# design.net
KiCad netlist of a schematic drawn in Altium Designer
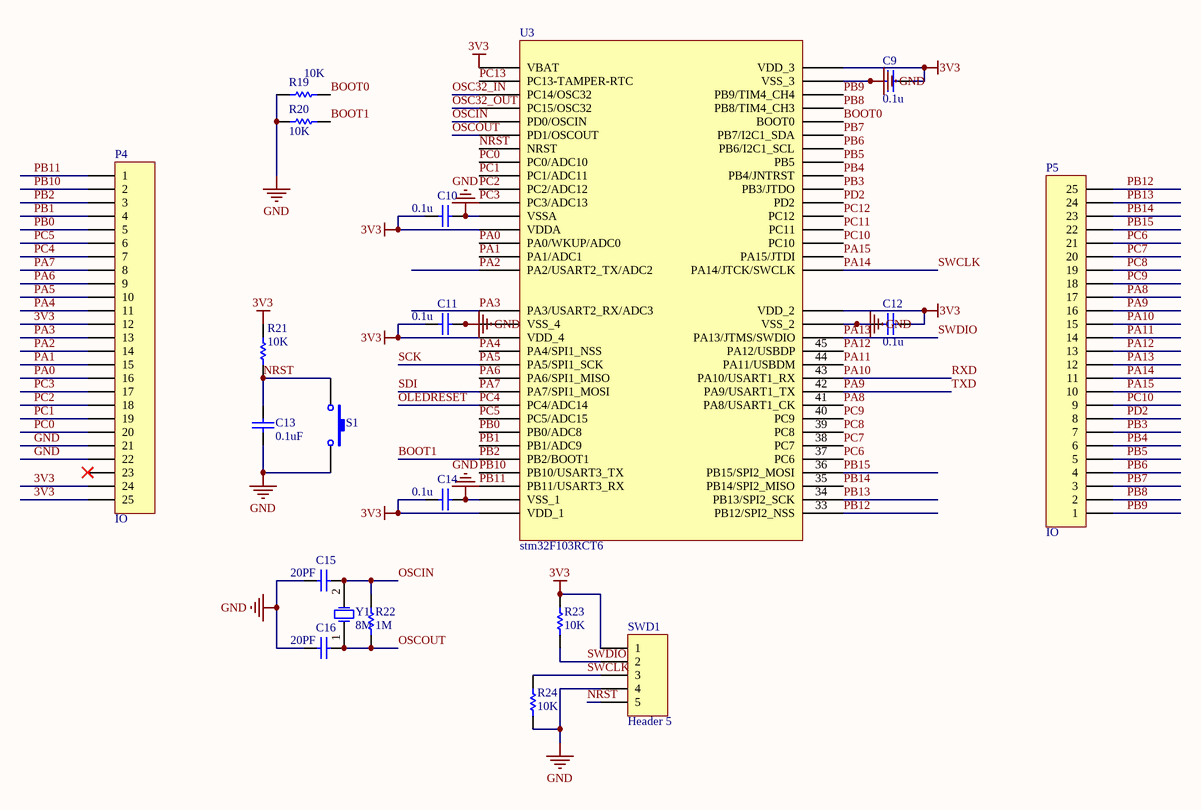
[diagram p0: 最小系统.SchDoc]

(export (version "E")
  (design (tool "Eeschema 10.0.6"))
  (components
    (comp (ref "C9")
      (value "0.1u")
      (footprint "CAP-MLCC-0603")
      (description "Capacitor")
      (fields (field (name "Comment") "Cap") (field (name "PUBLISHER") "Altium Limited"))
      (libsource (lib "K60-mainboard-v3.1") (part "Cap_1"))
    )
    (comp (ref "C10")
      (value "0.1u")
      (footprint "CAP-MLCC-0603")
      (description "Capacitor")
      (fields (field (name "Comment") "Cap") (field (name "PUBLISHER") "Altium Limited"))
      (libsource (lib "K60-mainboard-v3.1") (part "Cap_1"))
    )
    (comp (ref "C11")
      (value "0.1u")
      (footprint "CAP-MLCC-0603")
      (description "Capacitor")
      (fields (field (name "Comment") "Cap") (field (name "PUBLISHER") "Altium Limited"))
      (libsource (lib "K60-mainboard-v3.1") (part "Cap_1"))
    )
    (comp (ref "C12")
      (value "0.1u")
      (footprint "CAP-MLCC-0603")
      (description "Capacitor")
      (fields (field (name "Comment") "Cap") (field (name "PUBLISHER") "Altium Limited"))
      (libsource (lib "K60-mainboard-v3.1") (part "Cap_1"))
    )
    (comp (ref "C13")
      (value "0.1uF")
      (footprint "CAP-MLCC-0603")
      (description "Capacitor")
      (fields (field (name "Comment") "Cap") (field (name "PUBLISHER") "Altium Limited"))
      (libsource (lib "K60-mainboard-v3.1") (part "Cap"))
    )
    (comp (ref "C14")
      (value "0.1u")
      (footprint "CAP-MLCC-0603")
      (description "Capacitor")
      (fields (field (name "Comment") "Cap") (field (name "PUBLISHER") "Altium Limited"))
      (libsource (lib "K60-mainboard-v3.1") (part "Cap_1"))
    )
    (comp (ref "C15")
      (value "20PF")
      (footprint "CAP-MLCC-0603")
      (description "Capacitor")
      (fields (field (name "Comment") "Cap") (field (name "PUBLISHER") "Altium Limited"))
      (libsource (lib "K60-mainboard-v3.1") (part "Cap_1"))
    )
    (comp (ref "C16")
      (value "20PF")
      (footprint "CAP-MLCC-0603")
      (description "Capacitor")
      (fields (field (name "Comment") "Cap") (field (name "PUBLISHER") "Altium Limited"))
      (libsource (lib "K60-mainboard-v3.1") (part "Cap_1"))
    )
    (comp (ref "P4")
      (value "IO")
      (footprint "Header 25")
      (description "Header, 25-Pin")
      (fields (field (name "PUBLISHER") "Altium Limited"))
      (libsource (lib "") (part "Header 25_1"))
    )
    (comp (ref "P5")
      (value "IO")
      (footprint "Header 25")
      (description "Header, 25-Pin")
      (fields (field (name "PUBLISHER") "Altium Limited"))
      (libsource (lib "Libraries_2014_0618") (part "Header 25"))
    )
    (comp (ref "R19")
      (value "10K")
      (footprint "RES-0603")
      (description "Resistor")
      (fields (field (name "Comment") "Res1") (field (name "PUBLISHER") "Altium Limited"))
      (libsource (lib "K60-mainboard-v3.1") (part "Res1_1"))
    )
    (comp (ref "R20")
      (value "10K")
      (footprint "RES-0603")
      (description "Resistor")
      (fields (field (name "Comment") "Res1") (field (name "PUBLISHER") "Altium Limited"))
      (libsource (lib "K60-mainboard-v3.1") (part "Res1_1"))
    )
    (comp (ref "R21")
      (value "10K")
      (footprint "RES-0603")
      (description "Resistor")
      (fields (field (name "Comment") "Res1") (field (name "PUBLISHER") "Altium Limited"))
      (libsource (lib "K60-mainboard-v3.1") (part "Res1_1"))
    )
    (comp (ref "R22")
      (value "1M")
      (footprint "RES-0603")
      (description "Resistor")
      (fields (field (name "Comment") "Res1") (field (name "PUBLISHER") "Altium Limited"))
      (libsource (lib "K60-mainboard-v3.1") (part "Res1_1"))
    )
    (comp (ref "R23")
      (value "10K")
      (footprint "RES-0603")
      (description "Resistor")
      (fields (field (name "Comment") "Res1") (field (name "PUBLISHER") "Altium Limited"))
      (libsource (lib "K60-mainboard-v3.1") (part "Res1_1"))
    )
    (comp (ref "R24")
      (value "10K")
      (footprint "RES-0603")
      (description "Resistor")
      (fields (field (name "Comment") "Res1") (field (name "PUBLISHER") "Altium Limited"))
      (libsource (lib "K60-mainboard-v3.1") (part "Res1_1"))
    )
    (comp (ref "S1")
      (value "SW-PB")
      (footprint "key - duplicate")
      (description "Switch")
      (fields (field (name "PUBLISHER") "Altium Limited"))
      (libsource (lib "附加元件") (part "SW-PB"))
    )
    (comp (ref "SWD1")
      (value "Header 5")
      (footprint "HDR1X5")
      (description "Header, 5-Pin")
      (fields (field (name "PUBLISHER") "Altium Limited"))
      (libsource (lib "K60-mainboard-v3.1") (part "Header 5"))
    )
    (comp (ref "U3")
      (value "stm32F103RCT6")
      (footprint "STM32F103RCT6")
      (libsource (lib "K60-mainboard-v3.1") (part "stm32F103RCT6"))
    )
    (comp (ref "Y1")
      (value "8M")
      (footprint "Libraries_2014_0618:Osc-6032")
      (description "Crystal Oscillator")
      (fields (field (name "PUBLISHER") "Altium Limited"))
      (libsource (lib "Libraries_2014_0618") (part "C-Osc"))
    )
  )
  (nets
    (net (code "1") (name "/BOOT0") (class "Default")
      (node (ref "R19") (pin "1") (pinfunction "1_1") (pintype "passive"))
      (node (ref "U3") (pin "60") (pinfunction "BOOT0_60") (pintype "passive"))
    )
    (net (code "2") (name "/BOOT1") (class "Default")
      (node (ref "P4") (pin "3") (pinfunction "3_3") (pintype "passive"))
      (node (ref "R20") (pin "1") (pinfunction "1_1") (pintype "passive"))
      (node (ref "U3") (pin "28") (pinfunction "PB2/BOOT1_28") (pintype "passive"))
    )
    (net (code "3") (name "/NRST") (class "Default")
      (node (ref "C13") (pin "1") (pinfunction "1_1") (pintype "passive"))
      (node (ref "R21") (pin "1") (pinfunction "1_1") (pintype "passive"))
      (node (ref "S1") (pin "1") (pinfunction "1_1") (pintype "passive"))
      (node (ref "SWD1") (pin "5") (pinfunction "5_5") (pintype "passive"))
      (node (ref "U3") (pin "7") (pinfunction "NRST_7") (pintype "passive"))
    )
    (net (code "4") (name "/OLEDRESET") (class "Default")
      (node (ref "P4") (pin "7") (pinfunction "7_7") (pintype "passive"))
      (node (ref "U3") (pin "24") (pinfunction "PC4/ADC14_24") (pintype "passive"))
    )
    (net (code "5") (name "/OSC32_IN") (class "Default")
      (node (ref "U3") (pin "3") (pinfunction "PC14/OSC32_3") (pintype "passive"))
    )
    (net (code "6") (name "/OSC32_OUT") (class "Default")
      (node (ref "U3") (pin "4") (pinfunction "PC15/OSC32_4") (pintype "passive"))
    )
    (net (code "7") (name "/OSCIN") (class "Default")
      (node (ref "C15") (pin "2") (pinfunction "2_2") (pintype "passive"))
      (node (ref "R22") (pin "2") (pinfunction "2_2") (pintype "passive"))
      (node (ref "U3") (pin "5") (pinfunction "PD0/OSCIN_5") (pintype "passive"))
      (node (ref "Y1") (pin "2") (pinfunction "OSC2_2") (pintype "passive"))
    )
    (net (code "8") (name "/OSCOUT") (class "Default")
      (node (ref "C16") (pin "2") (pinfunction "2_2") (pintype "passive"))
      (node (ref "R22") (pin "1") (pinfunction "1_1") (pintype "passive"))
      (node (ref "U3") (pin "6") (pinfunction "PD1/OSCOUT_6") (pintype "passive"))
      (node (ref "Y1") (pin "1") (pinfunction "OSC1_1") (pintype "passive"))
    )
    (net (code "9") (name "/PA0") (class "Default")
      (node (ref "P4") (pin "16") (pinfunction "16_16") (pintype "passive"))
      (node (ref "U3") (pin "14") (pinfunction "PA0/WKUP/ADC0_14") (pintype "passive"))
    )
    (net (code "10") (name "/PA1") (class "Default")
      (node (ref "P4") (pin "15") (pinfunction "15_15") (pintype "passive"))
      (node (ref "U3") (pin "15") (pinfunction "PA1/ADC1_15") (pintype "passive"))
    )
    (net (code "11") (name "/PA2") (class "Default")
      (node (ref "P4") (pin "14") (pinfunction "14_14") (pintype "passive"))
      (node (ref "U3") (pin "16") (pinfunction "PA2/USART2_TX/ADC2_16") (pintype "passive"))
    )
    (net (code "12") (name "/PA3") (class "Default")
      (node (ref "P4") (pin "13") (pinfunction "13_13") (pintype "passive"))
      (node (ref "U3") (pin "17") (pinfunction "PA3/USART2_RX/ADC3_17") (pintype "passive"))
    )
    (net (code "13") (name "/PA4") (class "Default")
      (node (ref "P4") (pin "11") (pinfunction "11_11") (pintype "passive"))
      (node (ref "U3") (pin "20") (pinfunction "PA4/SPI1_NSS_20") (pintype "passive"))
    )
    (net (code "14") (name "/PA5") (class "Default")
      (node (ref "P4") (pin "10") (pinfunction "10_10") (pintype "passive"))
      (node (ref "U3") (pin "21") (pinfunction "PA5/SPI1_SCK_21") (pintype "passive"))
    )
    (net (code "15") (name "/PA6") (class "Default")
      (node (ref "P4") (pin "9") (pinfunction "9_9") (pintype "passive"))
      (node (ref "U3") (pin "22") (pinfunction "PA6/SPI1_MISO_22") (pintype "passive"))
    )
    (net (code "16") (name "/PA7") (class "Default")
      (node (ref "P4") (pin "8") (pinfunction "8_8") (pintype "passive"))
      (node (ref "U3") (pin "23") (pinfunction "PA7/SPI1_MOSI_23") (pintype "passive"))
    )
    (net (code "17") (name "/PA8") (class "Default")
      (node (ref "P5") (pin "17") (pinfunction "17_17") (pintype "passive"))
      (node (ref "U3") (pin "41") (pinfunction "PA8/USART1_CK_41") (pintype "passive"))
    )
    (net (code "18") (name "/PA9") (class "Default")
      (node (ref "P5") (pin "16") (pinfunction "16_16") (pintype "passive"))
      (node (ref "U3") (pin "42") (pinfunction "PA9/USART1_TX_42") (pintype "passive"))
    )
    (net (code "19") (name "/PA10") (class "Default")
      (node (ref "P5") (pin "15") (pinfunction "15_15") (pintype "passive"))
      (node (ref "U3") (pin "43") (pinfunction "PA10/USART1_RX_43") (pintype "passive"))
    )
    (net (code "20") (name "/PA11") (class "Default")
      (node (ref "P5") (pin "14") (pinfunction "14_14") (pintype "passive"))
      (node (ref "U3") (pin "44") (pinfunction "PA11/USBDM_44") (pintype "passive"))
    )
    (net (code "21") (name "/PA12") (class "Default")
      (node (ref "P5") (pin "13") (pinfunction "13_13") (pintype "passive"))
      (node (ref "U3") (pin "45") (pinfunction "PA12/USBDP_45") (pintype "passive"))
    )
    (net (code "22") (name "/PA13") (class "Default")
      (node (ref "P5") (pin "12") (pinfunction "12_12") (pintype "passive"))
      (node (ref "R23") (pin "1") (pinfunction "1_1") (pintype "passive"))
      (node (ref "SWD1") (pin "2") (pinfunction "2_2") (pintype "passive"))
      (node (ref "U3") (pin "46") (pinfunction "PA13/JTMS/SWDIO_46") (pintype "passive"))
    )
    (net (code "23") (name "/PA14") (class "Default")
      (node (ref "P5") (pin "11") (pinfunction "11_11") (pintype "passive"))
      (node (ref "R24") (pin "1") (pinfunction "1_1") (pintype "passive"))
      (node (ref "SWD1") (pin "3") (pinfunction "3_3") (pintype "passive"))
      (node (ref "U3") (pin "49") (pinfunction "PA14/JTCK/SWCLK_49") (pintype "passive"))
    )
    (net (code "24") (name "/PA15") (class "Default")
      (node (ref "P5") (pin "10") (pinfunction "10_10") (pintype "passive"))
      (node (ref "U3") (pin "50") (pinfunction "PA15/JTDI_50") (pintype "passive"))
    )
    (net (code "25") (name "/PB0") (class "Default")
      (node (ref "P4") (pin "5") (pinfunction "5_5") (pintype "passive"))
      (node (ref "U3") (pin "26") (pinfunction "PB0/ADC8_26") (pintype "passive"))
    )
    (net (code "26") (name "/PB1") (class "Default")
      (node (ref "P4") (pin "4") (pinfunction "4_4") (pintype "passive"))
      (node (ref "U3") (pin "27") (pinfunction "PB1/ADC9_27") (pintype "passive"))
    )
    (net (code "27") (name "/PB3") (class "Default")
      (node (ref "P5") (pin "7") (pinfunction "7_7") (pintype "passive"))
      (node (ref "U3") (pin "55") (pinfunction "PB3/JTDO_55") (pintype "passive"))
    )
    (net (code "28") (name "/PB4") (class "Default")
      (node (ref "P5") (pin "6") (pinfunction "6_6") (pintype "passive"))
      (node (ref "U3") (pin "56") (pinfunction "PB4/JNTRST_56") (pintype "passive"))
    )
    (net (code "29") (name "/PB5") (class "Default")
      (node (ref "P5") (pin "5") (pinfunction "5_5") (pintype "passive"))
      (node (ref "U3") (pin "57") (pinfunction "PB5_57") (pintype "passive"))
    )
    (net (code "30") (name "/PB6") (class "Default")
      (node (ref "P5") (pin "4") (pinfunction "4_4") (pintype "passive"))
      (node (ref "U3") (pin "58") (pinfunction "PB6/I2C1_SCL_58") (pintype "passive"))
    )
    (net (code "31") (name "/PB7") (class "Default")
      (node (ref "P5") (pin "3") (pinfunction "3_3") (pintype "passive"))
      (node (ref "U3") (pin "59") (pinfunction "PB7/I2C1_SDA_59") (pintype "passive"))
    )
    (net (code "32") (name "/PB8") (class "Default")
      (node (ref "P5") (pin "2") (pinfunction "2_2") (pintype "passive"))
      (node (ref "U3") (pin "61") (pinfunction "PB8/TIM4_CH3_61") (pintype "passive"))
    )
    (net (code "33") (name "/PB9") (class "Default")
      (node (ref "P5") (pin "1") (pinfunction "1_1") (pintype "passive"))
      (node (ref "U3") (pin "62") (pinfunction "PB9/TIM4_CH4_62") (pintype "passive"))
    )
    (net (code "34") (name "/PB10") (class "Default")
      (node (ref "P4") (pin "2") (pinfunction "2_2") (pintype "passive"))
      (node (ref "U3") (pin "29") (pinfunction "PB10/USART3_TX_29") (pintype "passive"))
    )
    (net (code "35") (name "/PB11") (class "Default")
      (node (ref "P4") (pin "1") (pinfunction "1_1") (pintype "passive"))
      (node (ref "U3") (pin "30") (pinfunction "PB11/USART3_RX_30") (pintype "passive"))
    )
    (net (code "36") (name "/PB12") (class "Default")
      (node (ref "P5") (pin "25") (pinfunction "25_25") (pintype "passive"))
      (node (ref "U3") (pin "33") (pinfunction "PB12/SPI2_NSS_33") (pintype "passive"))
    )
    (net (code "37") (name "/PB13") (class "Default")
      (node (ref "P5") (pin "24") (pinfunction "24_24") (pintype "passive"))
      (node (ref "U3") (pin "34") (pinfunction "PB13/SPI2_SCK_34") (pintype "passive"))
    )
    (net (code "38") (name "/PB14") (class "Default")
      (node (ref "P5") (pin "23") (pinfunction "23_23") (pintype "passive"))
      (node (ref "U3") (pin "35") (pinfunction "PB14/SPI2_MISO_35") (pintype "passive"))
    )
    (net (code "39") (name "/PB15") (class "Default")
      (node (ref "P5") (pin "22") (pinfunction "22_22") (pintype "passive"))
      (node (ref "U3") (pin "36") (pinfunction "PB15/SPI2_MOSI_36") (pintype "passive"))
    )
    (net (code "40") (name "/PC0") (class "Default")
      (node (ref "P4") (pin "20") (pinfunction "20_20") (pintype "passive"))
      (node (ref "U3") (pin "8") (pinfunction "PC0/ADC10_8") (pintype "passive"))
    )
    (net (code "41") (name "/PC1") (class "Default")
      (node (ref "P4") (pin "19") (pinfunction "19_19") (pintype "passive"))
      (node (ref "U3") (pin "9") (pinfunction "PC1/ADC11_9") (pintype "passive"))
    )
    (net (code "42") (name "/PC2") (class "Default")
      (node (ref "P4") (pin "18") (pinfunction "18_18") (pintype "passive"))
      (node (ref "U3") (pin "10") (pinfunction "PC2/ADC12_10") (pintype "passive"))
    )
    (net (code "43") (name "/PC3") (class "Default")
      (node (ref "P4") (pin "17") (pinfunction "17_17") (pintype "passive"))
      (node (ref "U3") (pin "11") (pinfunction "PC3/ADC13_11") (pintype "passive"))
    )
    (net (code "44") (name "/PC5") (class "Default")
      (node (ref "P4") (pin "6") (pinfunction "6_6") (pintype "passive"))
      (node (ref "U3") (pin "25") (pinfunction "PC5/ADC15_25") (pintype "passive"))
    )
    (net (code "45") (name "/PC6") (class "Default")
      (node (ref "P5") (pin "21") (pinfunction "21_21") (pintype "passive"))
      (node (ref "U3") (pin "37") (pinfunction "PC6_37") (pintype "passive"))
    )
    (net (code "46") (name "/PC7") (class "Default")
      (node (ref "P5") (pin "20") (pinfunction "20_20") (pintype "passive"))
      (node (ref "U3") (pin "38") (pinfunction "PC7_38") (pintype "passive"))
    )
    (net (code "47") (name "/PC8") (class "Default")
      (node (ref "P5") (pin "19") (pinfunction "19_19") (pintype "passive"))
      (node (ref "U3") (pin "39") (pinfunction "PC8_39") (pintype "passive"))
    )
    (net (code "48") (name "/PC9") (class "Default")
      (node (ref "P5") (pin "18") (pinfunction "18_18") (pintype "passive"))
      (node (ref "U3") (pin "40") (pinfunction "PC9_40") (pintype "passive"))
    )
    (net (code "49") (name "/PC10") (class "Default")
      (node (ref "P5") (pin "9") (pinfunction "9_9") (pintype "passive"))
      (node (ref "U3") (pin "51") (pinfunction "PC10_51") (pintype "passive"))
    )
    (net (code "50") (name "/PC11") (class "Default")
      (node (ref "U3") (pin "52") (pinfunction "PC11_52") (pintype "passive"))
    )
    (net (code "51") (name "/PC12") (class "Default")
      (node (ref "U3") (pin "53") (pinfunction "PC12_53") (pintype "passive"))
    )
    (net (code "52") (name "/PC13") (class "Default")
      (node (ref "U3") (pin "2") (pinfunction "PC13-TAMPER-RTC_2") (pintype "passive"))
    )
    (net (code "53") (name "/PD2") (class "Default")
      (node (ref "P5") (pin "8") (pinfunction "8_8") (pintype "passive"))
      (node (ref "U3") (pin "54") (pinfunction "PD2_54") (pintype "passive"))
    )
    (net (code "54") (name "3V3") (class "Default")
      (node (ref "C10") (pin "1") (pinfunction "1_1") (pintype "passive"))
      (node (ref "C11") (pin "1") (pinfunction "1_1") (pintype "passive"))
      (node (ref "C12") (pin "1") (pinfunction "1_1") (pintype "passive"))
      (node (ref "C14") (pin "1") (pinfunction "1_1") (pintype "passive"))
      (node (ref "C9") (pin "1") (pinfunction "1_1") (pintype "passive"))
      (node (ref "P4") (pin "12") (pinfunction "12_12") (pintype "passive"))
      (node (ref "P4") (pin "24") (pinfunction "24_24") (pintype "passive"))
      (node (ref "P4") (pin "25") (pinfunction "25_25") (pintype "passive"))
      (node (ref "R21") (pin "2") (pinfunction "2_2") (pintype "passive"))
      (node (ref "R23") (pin "2") (pinfunction "2_2") (pintype "passive"))
      (node (ref "SWD1") (pin "1") (pinfunction "1_1") (pintype "passive"))
      (node (ref "U3") (pin "1") (pinfunction "VBAT_1") (pintype "passive"))
      (node (ref "U3") (pin "13") (pinfunction "VDDA_13") (pintype "passive"))
      (node (ref "U3") (pin "19") (pinfunction "VDD_4_19") (pintype "passive"))
      (node (ref "U3") (pin "32") (pinfunction "VDD_1_32") (pintype "passive"))
      (node (ref "U3") (pin "48") (pinfunction "VDD_2_48") (pintype "passive"))
      (node (ref "U3") (pin "64") (pinfunction "VDD_3_64") (pintype "passive"))
    )
    (net (code "55") (name "GND") (class "Default")
      (node (ref "C10") (pin "2") (pinfunction "2_2") (pintype "passive"))
      (node (ref "C11") (pin "2") (pinfunction "2_2") (pintype "passive"))
      (node (ref "C12") (pin "2") (pinfunction "2_2") (pintype "passive"))
      (node (ref "C13") (pin "2") (pinfunction "2_2") (pintype "passive"))
      (node (ref "C14") (pin "2") (pinfunction "2_2") (pintype "passive"))
      (node (ref "C15") (pin "1") (pinfunction "1_1") (pintype "passive"))
      (node (ref "C16") (pin "1") (pinfunction "1_1") (pintype "passive"))
      (node (ref "C9") (pin "2") (pinfunction "2_2") (pintype "passive"))
      (node (ref "P4") (pin "21") (pinfunction "21_21") (pintype "passive"))
      (node (ref "P4") (pin "22") (pinfunction "22_22") (pintype "passive"))
      (node (ref "R19") (pin "2") (pinfunction "2_2") (pintype "passive"))
      (node (ref "R20") (pin "2") (pinfunction "2_2") (pintype "passive"))
      (node (ref "R24") (pin "2") (pinfunction "2_2") (pintype "passive"))
      (node (ref "S1") (pin "2") (pinfunction "2_2") (pintype "passive"))
      (node (ref "SWD1") (pin "4") (pinfunction "4_4") (pintype "passive"))
      (node (ref "U3") (pin "12") (pinfunction "VSSA_12") (pintype "passive"))
      (node (ref "U3") (pin "18") (pinfunction "VSS_4_18") (pintype "passive"))
      (node (ref "U3") (pin "31") (pinfunction "VSS_1_31") (pintype "passive"))
      (node (ref "U3") (pin "47") (pinfunction "VSS_2_47") (pintype "passive"))
      (node (ref "U3") (pin "63") (pinfunction "VSS_3_63") (pintype "passive"))
    )
    (net (code "56") (name "unconnected-(P4-Pad23)") (class "Default")
      (node (ref "P4") (pin "23") (pinfunction "23_23") (pintype "passive+no_connect"))
    )
  )
)
